# Adafruit_CC3000_Breakout.net
KiCad netlist of a schematic drawn in EAGLE
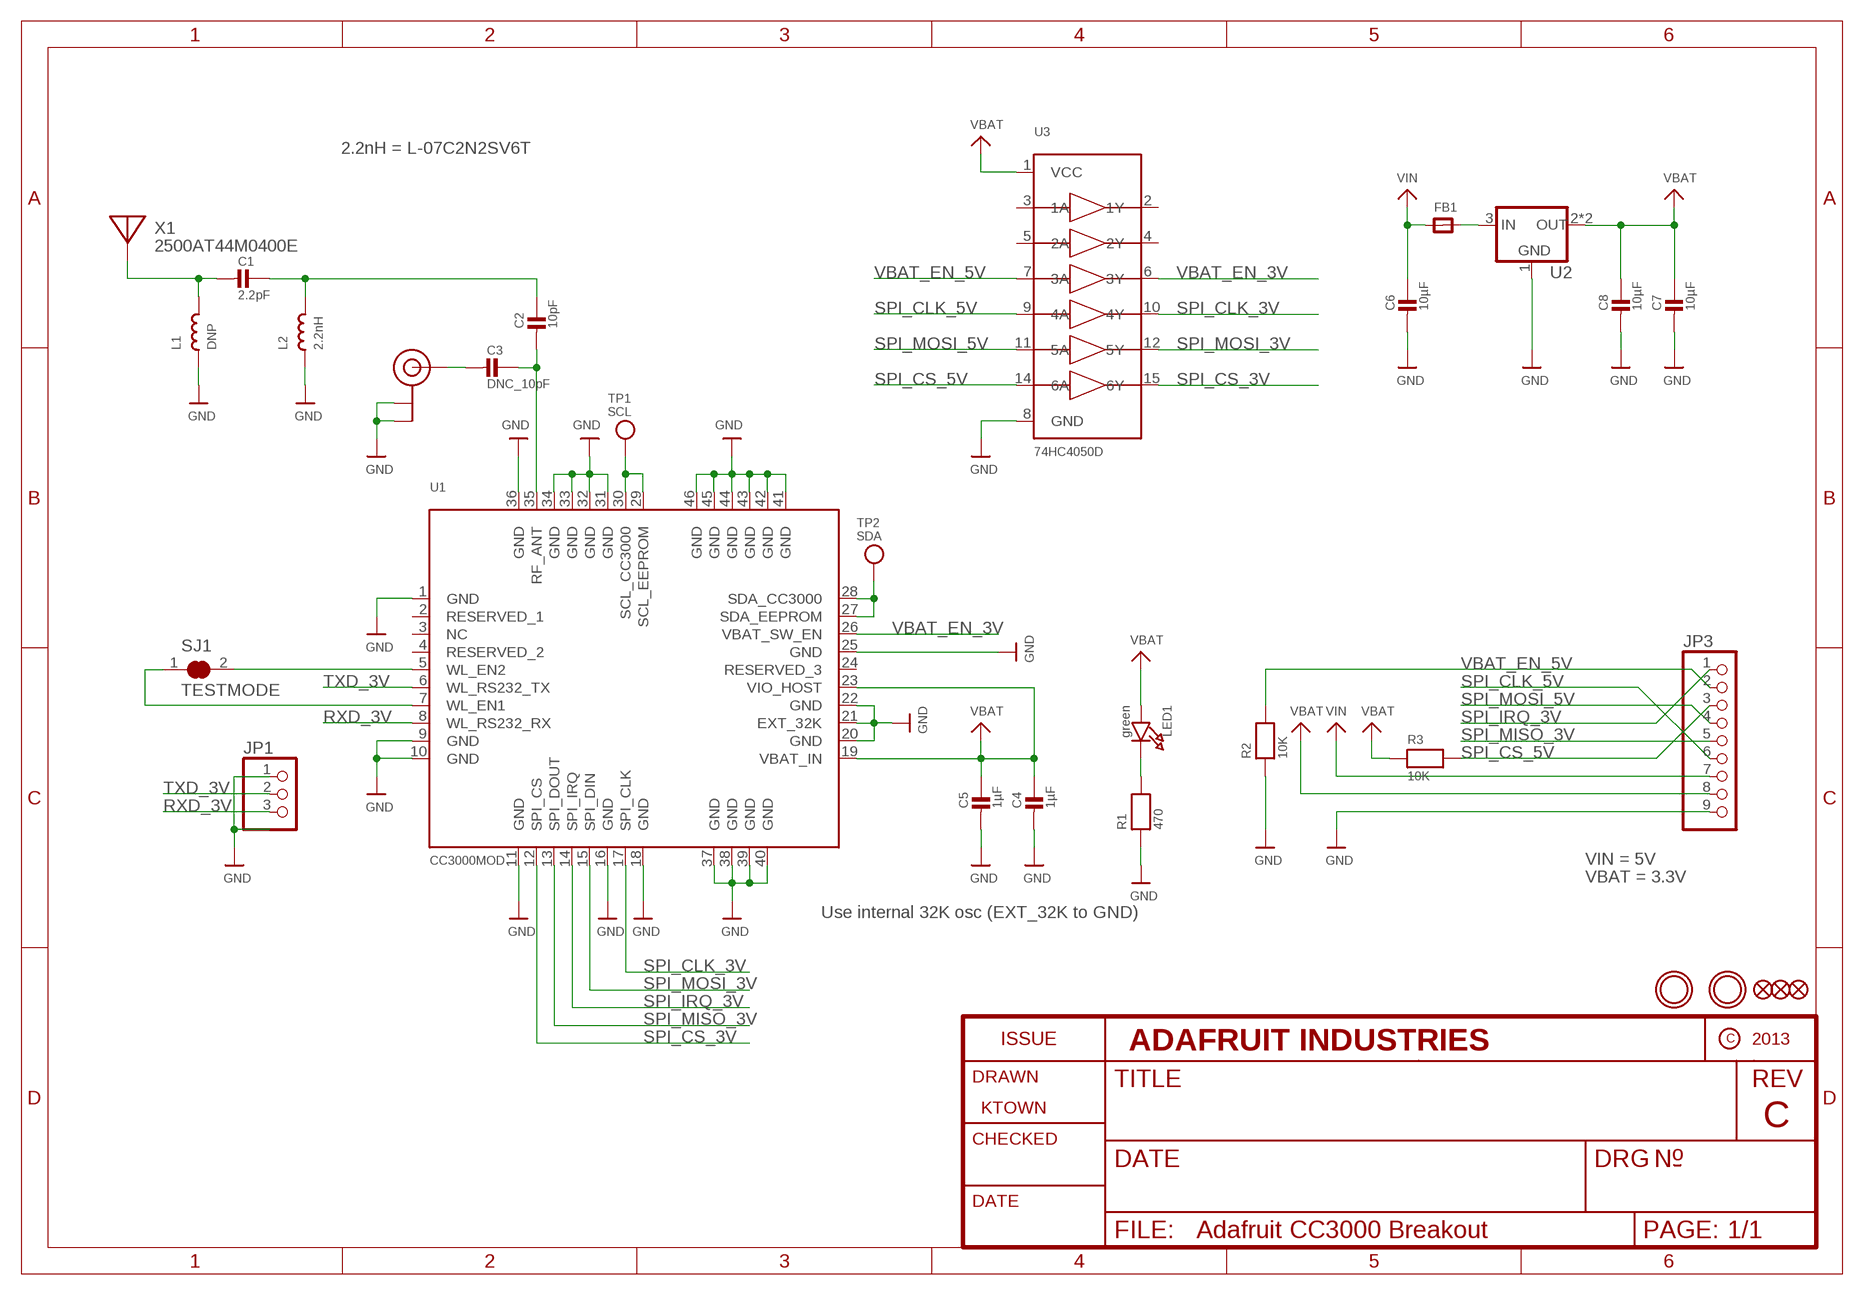
[diagram p0: schematic, sheet 1]

(export (version "E")
  (design (tool "Eeschema 10.0.6"))
  (components
    (comp (ref "C1")
      (value "2.2pF")
      (footprint "eagle-import:_0402")
      (libsource (lib "eagle-import") (part "CAP_CERAMIC_0402"))
    )
    (comp (ref "C2")
      (value "10pF")
      (footprint "eagle-import:_0402")
      (libsource (lib "eagle-import") (part "CAP_CERAMIC_0402"))
    )
    (comp (ref "C3")
      (value "DNC_10pF")
      (footprint "eagle-import:_0402")
      (libsource (lib "eagle-import") (part "CAP_CERAMIC_0402"))
    )
    (comp (ref "C4")
      (value "1µF")
      (footprint "eagle-import:_0805MP")
      (libsource (lib "eagle-import") (part "CAP_CERAMIC_0805MP"))
    )
    (comp (ref "C5")
      (value "1µF")
      (footprint "eagle-import:_0805MP")
      (libsource (lib "eagle-import") (part "CAP_CERAMIC_0805MP"))
    )
    (comp (ref "C6")
      (value "10µF")
      (footprint "eagle-import:_0805MP")
      (libsource (lib "eagle-import") (part "CAP_CERAMIC_0805MP"))
    )
    (comp (ref "C7")
      (value "10µF")
      (footprint "eagle-import:_0805MP")
      (libsource (lib "eagle-import") (part "CAP_CERAMIC_0805MP"))
    )
    (comp (ref "C8")
      (value "10µF")
      (footprint "eagle-import:_0805MP")
      (libsource (lib "eagle-import") (part "CAP_CERAMIC_0805MP"))
    )
    (comp (ref "FB1")
      (value "FERRITE_0805MP")
      (footprint "eagle-import:_0805MP")
      (libsource (lib "eagle-import") (part "FERRITE_0805MP"))
    )
    (comp (ref "FID1")
      (value "FIDUCIAL\"\"")
      (footprint "eagle-import:FIDUCIAL_1MM")
      (libsource (lib "eagle-import") (part "FIDUCIAL{dblquote}{dblquote}"))
    )
    (comp (ref "FID2")
      (value "FIDUCIAL\"\"")
      (footprint "eagle-import:FIDUCIAL_1MM")
      (libsource (lib "eagle-import") (part "FIDUCIAL{dblquote}{dblquote}"))
    )
    (comp (ref "FID3")
      (value "FIDUCIAL\"\"")
      (footprint "eagle-import:FIDUCIAL_1MM")
      (fields (field (name "BOM") "EXCLUDE"))
      (libsource (lib "eagle-import") (part "FIDUCIAL{dblquote}{dblquote}"))
    )
    (comp (ref "JP1")
      (value "HEADER-1X3ROUND")
      (footprint "eagle-import:1X03_ROUND")
      (libsource (lib "eagle-import") (part "HEADER-1X3ROUND"))
    )
    (comp (ref "JP3")
      (value "HEADER-1X970MIL")
      (footprint "eagle-import:1X09_ROUND_70")
      (libsource (lib "eagle-import") (part "HEADER-1X970MIL"))
    )
    (comp (ref "L1")
      (value "DNP")
      (footprint "eagle-import:_0402")
      (libsource (lib "eagle-import") (part "INDUCTOR_0402"))
    )
    (comp (ref "L2")
      (value "2.2nH")
      (footprint "eagle-import:_0402")
      (libsource (lib "eagle-import") (part "INDUCTOR_0402"))
    )
    (comp (ref "LED1")
      (value "green")
      (footprint "eagle-import:CHIPLED_0805_NOOUTLINE")
      (libsource (lib "eagle-import") (part "LED0805_NOOUTLINE"))
    )
    (comp (ref "R1")
      (value "470")
      (footprint "eagle-import:0805-NO")
      (libsource (lib "eagle-import") (part "RESISTOR0805_NOOUTLINE"))
    )
    (comp (ref "R2")
      (value "10K")
      (footprint "eagle-import:_0805MP")
      (libsource (lib "eagle-import") (part "RESISTOR_0805MP"))
    )
    (comp (ref "R3")
      (value "10K")
      (footprint "eagle-import:_0805MP")
      (libsource (lib "eagle-import") (part "RESISTOR_0805MP"))
    )
    (comp (ref "SJ1")
      (value "TESTMODE")
      (footprint "eagle-import:SOLDERJUMPER_CLOSEDWIRE")
      (libsource (lib "eagle-import") (part "SOLDERJUMPER_CLOSED"))
    )
    (comp (ref "TP1")
      (value "SCL")
      (footprint "eagle-import:TESTPOINT_PAD_1MM")
      (libsource (lib "eagle-import") (part "TESTPOINTPAD1MM"))
    )
    (comp (ref "TP2")
      (value "SDA")
      (footprint "eagle-import:TESTPOINT_PAD_1MM")
      (libsource (lib "eagle-import") (part "TESTPOINTPAD1MM"))
    )
    (comp (ref "U$24")
      (value "MOUNTINGHOLE2.5")
      (footprint "eagle-import:MOUNTINGHOLE_2.5_PLATED")
      (libsource (lib "eagle-import") (part "MOUNTINGHOLE2.5"))
    )
    (comp (ref "U$34")
      (value "MOUNTINGHOLE2.5")
      (footprint "eagle-import:MOUNTINGHOLE_2.5_PLATED")
      (libsource (lib "eagle-import") (part "MOUNTINGHOLE2.5"))
    )
    (comp (ref "U$35")
      (value "U.FL")
      (footprint "eagle-import:U.FL")
      (libsource (lib "eagle-import") (part "U.FL"))
    )
    (comp (ref "U1")
      (value "CC3000MOD")
      (footprint "eagle-import:CC3000MOD")
      (libsource (lib "eagle-import") (part "CC3000MOD"))
    )
    (comp (ref "U2")
      (value "VREG_SOT223")
      (footprint "eagle-import:SOT223-R")
      (libsource (lib "eagle-import") (part "VREG_SOT223"))
    )
    (comp (ref "U3")
      (value "74HC4050D")
      (footprint "eagle-import:SOIC16")
      (libsource (lib "eagle-import") (part "74HC4050D"))
    )
    (comp (ref "X1")
      (value "2500AT44M0400E")
      (footprint "eagle-import:ANT_2500AT44M0400")
      (libsource (lib "eagle-import") (part "ANTENNA_JOHANSON_2500AT44M0400"))
    )
  )
  (nets
    (net (code "1") (name "/RXD_3V") (class "Default")
      (node (ref "JP1") (pin "3") (pinfunction "3_3") (pintype "passive"))
      (node (ref "U1") (pin "8") (pinfunction "WL_RS232_RX_8") (pintype "input"))
    )
    (net (code "2") (name "/SPI_CLK_3V") (class "Default")
      (node (ref "U1") (pin "17") (pinfunction "SPI_CLK_17") (pintype "input"))
      (node (ref "U3") (pin "10") (pinfunction "4Y_10") (pintype "bidirectional"))
    )
    (net (code "3") (name "/SPI_CLK_5V") (class "Default")
      (node (ref "JP3") (pin "6") (pinfunction "6_6") (pintype "passive"))
      (node (ref "U3") (pin "9") (pinfunction "4A_9") (pintype "bidirectional"))
    )
    (net (code "4") (name "/SPI_CS_3V") (class "Default")
      (node (ref "U1") (pin "12") (pinfunction "SPI_CS_12") (pintype "input"))
      (node (ref "U3") (pin "15") (pinfunction "6Y_15") (pintype "bidirectional"))
    )
    (net (code "5") (name "/SPI_CS_5V") (class "Default")
      (node (ref "JP3") (pin "3") (pinfunction "3_3") (pintype "passive"))
      (node (ref "R3") (pin "2") (pinfunction "2_2") (pintype "passive"))
      (node (ref "U3") (pin "14") (pinfunction "6A_14") (pintype "bidirectional"))
    )
    (net (code "6") (name "/SPI_IRQ_3V") (class "Default")
      (node (ref "JP3") (pin "1") (pinfunction "1_1") (pintype "passive"))
      (node (ref "U1") (pin "14") (pinfunction "SPI_IRQ_14") (pintype "output"))
    )
    (net (code "7") (name "/SPI_MISO_3V") (class "Default")
      (node (ref "JP3") (pin "5") (pinfunction "5_5") (pintype "passive"))
      (node (ref "U1") (pin "13") (pinfunction "SPI_DOUT_13") (pintype "output"))
    )
    (net (code "8") (name "/SPI_MOSI_3V") (class "Default")
      (node (ref "U1") (pin "15") (pinfunction "SPI_DIN_15") (pintype "input"))
      (node (ref "U3") (pin "12") (pinfunction "5Y_12") (pintype "bidirectional"))
    )
    (net (code "9") (name "/SPI_MOSI_5V") (class "Default")
      (node (ref "JP3") (pin "4") (pinfunction "4_4") (pintype "passive"))
      (node (ref "U3") (pin "11") (pinfunction "5A_11") (pintype "bidirectional"))
    )
    (net (code "10") (name "/TXD_3V") (class "Default")
      (node (ref "JP1") (pin "2") (pinfunction "2_2") (pintype "passive"))
      (node (ref "U1") (pin "6") (pinfunction "WL_RS232_TX_6") (pintype "output"))
    )
    (net (code "11") (name "/VBAT_EN_3V") (class "Default")
      (node (ref "U1") (pin "26") (pinfunction "VBAT_SW_EN_26") (pintype "input"))
      (node (ref "U3") (pin "6") (pinfunction "3Y_6") (pintype "bidirectional"))
    )
    (net (code "12") (name "/VBAT_EN_5V") (class "Default")
      (node (ref "JP3") (pin "2") (pinfunction "2_2") (pintype "passive"))
      (node (ref "R2") (pin "2") (pinfunction "2_2") (pintype "passive"))
      (node (ref "U3") (pin "7") (pinfunction "3A_7") (pintype "bidirectional"))
    )
    (net (code "13") (name "GND") (class "Default")
      (node (ref "C4") (pin "2") (pinfunction "2_2") (pintype "passive"))
      (node (ref "C5") (pin "2") (pinfunction "2_2") (pintype "passive"))
      (node (ref "C6") (pin "2") (pinfunction "2_2") (pintype "passive"))
      (node (ref "C7") (pin "2") (pinfunction "2_2") (pintype "passive"))
      (node (ref "C8") (pin "2") (pinfunction "2_2") (pintype "passive"))
      (node (ref "JP1") (pin "1") (pinfunction "1_1") (pintype "passive"))
      (node (ref "JP3") (pin "9") (pinfunction "9_9") (pintype "passive"))
      (node (ref "L1") (pin "1") (pinfunction "1_1") (pintype "passive"))
      (node (ref "L2") (pin "1") (pinfunction "1_1") (pintype "passive"))
      (node (ref "R1") (pin "1") (pinfunction "1_1") (pintype "passive"))
      (node (ref "R2") (pin "1") (pinfunction "1_1") (pintype "passive"))
      (node (ref "U$35") (pin "P$1") (pinfunction "GND_P$1") (pintype "bidirectional"))
      (node (ref "U$35") (pin "P$2") (pinfunction "GND_P$2") (pintype "bidirectional"))
      (node (ref "U1") (pin "1") (pinfunction "GND_1") (pintype "power_in"))
      (node (ref "U1") (pin "10") (pinfunction "GND_10") (pintype "power_in"))
      (node (ref "U1") (pin "11") (pinfunction "GND_11") (pintype "power_in"))
      (node (ref "U1") (pin "16") (pinfunction "GND_16") (pintype "power_in"))
      (node (ref "U1") (pin "18") (pinfunction "GND_18") (pintype "power_in"))
      (node (ref "U1") (pin "20") (pinfunction "GND_20") (pintype "power_in"))
      (node (ref "U1") (pin "21") (pinfunction "EXT_32K_21") (pintype "bidirectional"))
      (node (ref "U1") (pin "22") (pinfunction "GND_22") (pintype "power_in"))
      (node (ref "U1") (pin "25") (pinfunction "GND_25") (pintype "power_in"))
      (node (ref "U1") (pin "31") (pinfunction "GND_31") (pintype "power_in"))
      (node (ref "U1") (pin "32") (pinfunction "GND_32") (pintype "power_in"))
      (node (ref "U1") (pin "33") (pinfunction "GND_33") (pintype "power_in"))
      (node (ref "U1") (pin "34") (pinfunction "GND_34") (pintype "power_in"))
      (node (ref "U1") (pin "36") (pinfunction "GND_36") (pintype "power_in"))
      (node (ref "U1") (pin "37") (pinfunction "GND_37") (pintype "power_in"))
      (node (ref "U1") (pin "38") (pinfunction "GND_38") (pintype "power_in"))
      (node (ref "U1") (pin "39") (pinfunction "GND_39") (pintype "power_in"))
      (node (ref "U1") (pin "40") (pinfunction "GND_40") (pintype "power_in"))
      (node (ref "U1") (pin "41") (pinfunction "GND_41") (pintype "power_in"))
      (node (ref "U1") (pin "42") (pinfunction "GND_42") (pintype "power_in"))
      (node (ref "U1") (pin "43") (pinfunction "GND_43") (pintype "power_in"))
      (node (ref "U1") (pin "44") (pinfunction "GND_44") (pintype "power_in"))
      (node (ref "U1") (pin "45") (pinfunction "GND_45") (pintype "power_in"))
      (node (ref "U1") (pin "46") (pinfunction "GND_46") (pintype "power_in"))
      (node (ref "U1") (pin "9") (pinfunction "GND_9") (pintype "power_in"))
      (node (ref "U2") (pin "1") (pinfunction "GND_1") (pintype "power_in"))
      (node (ref "U3") (pin "8") (pinfunction "GND_8") (pintype "bidirectional"))
    )
    (net (code "14") (name "Net-(C1-Pad1)") (class "Default")
      (node (ref "C1") (pin "1") (pinfunction "1_1") (pintype "passive"))
      (node (ref "C2") (pin "1") (pinfunction "1_1") (pintype "passive"))
      (node (ref "L2") (pin "2") (pinfunction "2_2") (pintype "passive"))
    )
    (net (code "15") (name "Net-(FB1-P$2)") (class "Default")
      (node (ref "FB1") (pin "2") (pinfunction "P$2_2") (pintype "passive"))
      (node (ref "U2") (pin "3") (pinfunction "IN_3") (pintype "power_in"))
    )
    (net (code "16") (name "Net-(LED1-PadC)") (class "Default")
      (node (ref "LED1") (pin "C") (pinfunction "C_C") (pintype "passive"))
      (node (ref "R1") (pin "2") (pinfunction "2_2") (pintype "passive"))
    )
    (net (code "17") (name "Net-(U$35-SIGNAL)") (class "Default")
      (node (ref "C3") (pin "2") (pinfunction "2_2") (pintype "passive"))
      (node (ref "U$35") (pin "P$3") (pinfunction "SIGNAL_P$3") (pintype "bidirectional"))
    )
    (net (code "18") (name "Net-(U1-RF_ANT)") (class "Default")
      (node (ref "C2") (pin "2") (pinfunction "2_2") (pintype "passive"))
      (node (ref "C3") (pin "1") (pinfunction "1_1") (pintype "passive"))
      (node (ref "U1") (pin "35") (pinfunction "RF_ANT_35") (pintype "bidirectional"))
    )
    (net (code "19") (name "Net-(U1-SCL_CC3000)") (class "Default")
      (node (ref "TP1") (pin "P$1") (pinfunction "P$1_P$1") (pintype "bidirectional"))
      (node (ref "U1") (pin "29") (pinfunction "SCL_EEPROM_29") (pintype "bidirectional"))
      (node (ref "U1") (pin "30") (pinfunction "SCL_CC3000_30") (pintype "bidirectional"))
    )
    (net (code "20") (name "Net-(U1-SDA_CC3000)") (class "Default")
      (node (ref "TP2") (pin "P$1") (pinfunction "P$1_P$1") (pintype "bidirectional"))
      (node (ref "U1") (pin "27") (pinfunction "SDA_EEPROM_27") (pintype "bidirectional"))
      (node (ref "U1") (pin "28") (pinfunction "SDA_CC3000_28") (pintype "bidirectional"))
    )
    (net (code "21") (name "Net-(U1-WL_EN1)") (class "Default")
      (node (ref "SJ1") (pin "1") (pinfunction "1_1") (pintype "passive"))
      (node (ref "U1") (pin "7") (pinfunction "WL_EN1_7") (pintype "input"))
    )
    (net (code "22") (name "Net-(U1-WL_EN2)") (class "Default")
      (node (ref "SJ1") (pin "2") (pinfunction "2_2") (pintype "passive"))
      (node (ref "U1") (pin "5") (pinfunction "WL_EN2_5") (pintype "input"))
    )
    (net (code "23") (name "Net-(X1-P$1)") (class "Default")
      (node (ref "C1") (pin "2") (pinfunction "2_2") (pintype "passive"))
      (node (ref "L1") (pin "2") (pinfunction "2_2") (pintype "passive"))
      (node (ref "X1") (pin "FEED") (pinfunction "P$1_FEED") (pintype "passive"))
    )
    (net (code "24") (name "VBAT") (class "Default")
      (node (ref "C4") (pin "1") (pinfunction "1_1") (pintype "passive"))
      (node (ref "C5") (pin "1") (pinfunction "1_1") (pintype "passive"))
      (node (ref "C7") (pin "1") (pinfunction "1_1") (pintype "passive"))
      (node (ref "C8") (pin "1") (pinfunction "1_1") (pintype "passive"))
      (node (ref "JP3") (pin "8") (pinfunction "8_8") (pintype "passive"))
      (node (ref "LED1") (pin "A") (pinfunction "A_A") (pintype "passive"))
      (node (ref "R3") (pin "1") (pinfunction "1_1") (pintype "passive"))
      (node (ref "U1") (pin "19") (pinfunction "VBAT_IN_19") (pintype "power_in"))
      (node (ref "U1") (pin "23") (pinfunction "VIO_HOST_23") (pintype "power_in"))
      (node (ref "U2") (pin "2") (pinfunction "OUT_2") (pintype "power_in"))
      (node (ref "U2") (pin "4") (pinfunction "OUT_4") (pintype "power_in"))
      (node (ref "U3") (pin "1") (pinfunction "VCC_1") (pintype "bidirectional"))
    )
    (net (code "25") (name "VIN") (class "Default")
      (node (ref "C6") (pin "1") (pinfunction "1_1") (pintype "passive"))
      (node (ref "FB1") (pin "1") (pinfunction "P$1_1") (pintype "passive"))
      (node (ref "JP3") (pin "7") (pinfunction "7_7") (pintype "passive"))
    )
    (net (code "26") (name "unconnected-(U1-NC-Pad3)") (class "Default")
      (node (ref "U1") (pin "3") (pinfunction "NC_3") (pintype "no_connect"))
    )
    (net (code "27") (name "unconnected-(U1-RESERVED_1-Pad2)") (class "Default")
      (node (ref "U1") (pin "2") (pinfunction "RESERVED_1_2") (pintype "bidirectional"))
    )
    (net (code "28") (name "unconnected-(U1-RESERVED_2-Pad4)") (class "Default")
      (node (ref "U1") (pin "4") (pinfunction "RESERVED_2_4") (pintype "bidirectional"))
    )
    (net (code "29") (name "unconnected-(U1-RESERVED_3-Pad24)") (class "Default")
      (node (ref "U1") (pin "24") (pinfunction "RESERVED_3_24") (pintype "bidirectional"))
    )
    (net (code "30") (name "unconnected-(U3-1A-Pad3)") (class "Default")
      (node (ref "U3") (pin "3") (pinfunction "1A_3") (pintype "bidirectional"))
    )
    (net (code "31") (name "unconnected-(U3-1Y-Pad2)") (class "Default")
      (node (ref "U3") (pin "2") (pinfunction "1Y_2") (pintype "bidirectional"))
    )
    (net (code "32") (name "unconnected-(U3-2A-Pad5)") (class "Default")
      (node (ref "U3") (pin "5") (pinfunction "2A_5") (pintype "bidirectional"))
    )
    (net (code "33") (name "unconnected-(U3-2Y-Pad4)") (class "Default")
      (node (ref "U3") (pin "4") (pinfunction "2Y_4") (pintype "bidirectional"))
    )
  )
)
